# Esquematico.net
KiCad netlist of a schematic drawn in Altium Designer
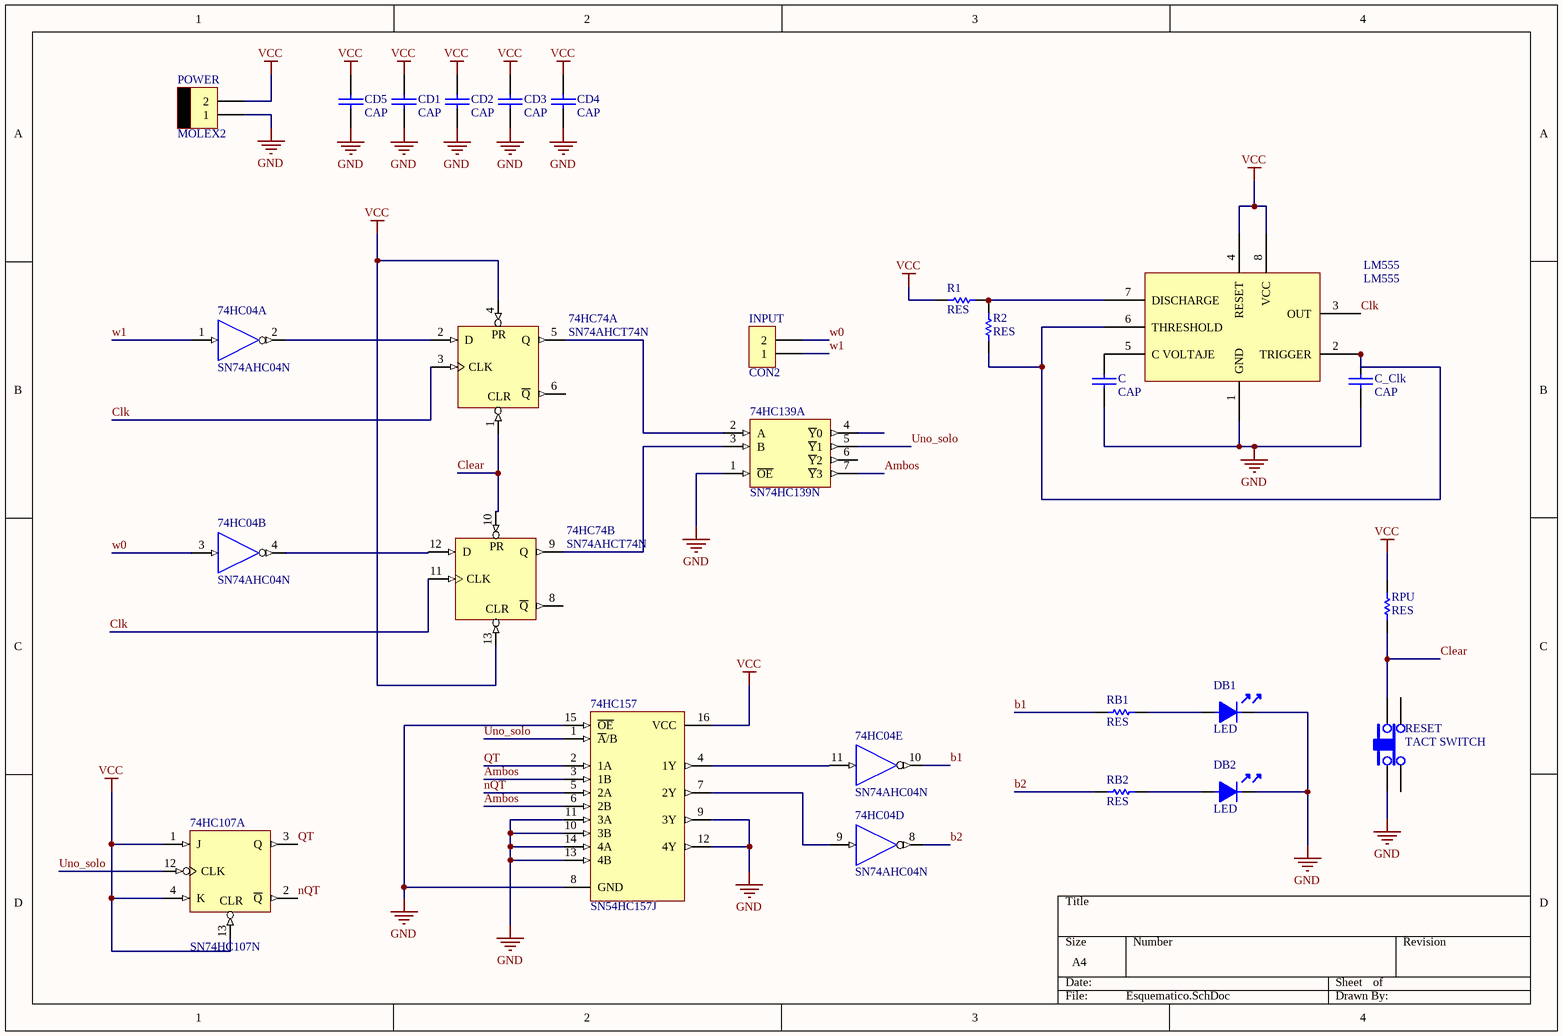
[diagram p0: Esquematico.SchDoc]

(export (version "E")
  (design (tool "Eeschema 10.0.6"))
  (components
    (comp (ref "74HC04")
      (value "SN74AHC04N")
      (footprint "N014")
      (description "Hex Inverter")
      (fields (field (name "PUBLISHER") "Altium Limited"))
      (libsource (lib "TI Logic Gate 1") (part "SN74AHC04N"))
    )
    (comp (ref "74HC74")
      (value "SN74AHCT74N")
      (footprint "N014")
      (description "Dual Positive-Edge-Triggered D-Type Flip-Flop with Clear and Preset")
      (fields (field (name "PUBLISHER") "Altium Limited"))
      (libsource (lib "TI Logic Flip-Flop") (part "SN74AHCT74N"))
    )
    (comp (ref "74HC107")
      (value "SN74HC107N")
      (footprint "N014D")
      (description "Dual J-K Negative-Edge-Triggered Flip-Flop with Clear")
      (fields (field (name "PUBLISHER") "Altium Limited"))
      (libsource (lib "TI Logic Flip-Flop") (part "SN74HC107N"))
    )
    (comp (ref "74HC139")
      (value "SN74HC139N")
      (footprint "N016")
      (description "Dual 2-Line to 4-Line Decoder / Demultiplexer")
      (fields (field (name "PUBLISHER") "Altium Limited"))
      (libsource (lib "TI Logic Decoder Demux") (part "SN74HC139N"))
    )
    (comp (ref "74HC157")
      (value "SN54HC157J")
      (footprint "J016")
      (description "Quadraple 2-Line to 1-Line Data Selector/Multiplexer")
      (fields (field (name "PUBLISHER") "Altium Limited"))
      (libsource (lib "TI Logic Multiplexer") (part "SN54HC157J"))
    )
    (comp (ref "C") (value "CAP") (footprint "CAP200") (libsource (lib "LIBEBAL") (part "CAP")))
    (comp (ref "CD1") (value "CAP") (footprint "CAP200") (libsource (lib "LIBEBAL") (part "CAP")))
    (comp (ref "CD2") (value "CAP") (footprint "CAP200") (libsource (lib "LIBEBAL") (part "CAP")))
    (comp (ref "CD3") (value "CAP") (footprint "CAP200") (libsource (lib "LIBEBAL") (part "CAP")))
    (comp (ref "CD4") (value "CAP") (footprint "CAP200") (libsource (lib "LIBEBAL") (part "CAP")))
    (comp (ref "CD5") (value "CAP") (footprint "CAP200") (libsource (lib "LIBEBAL") (part "CAP")))
    (comp (ref "C_Clk") (value "CAP") (footprint "CAP200") (libsource (lib "LIBEBAL") (part "CAP")))
    (comp (ref "DB1") (value "LED") (footprint "LED3") (libsource (lib "LIBEBAL") (part "LED")))
    (comp (ref "DB2") (value "LED") (footprint "LED3") (libsource (lib "LIBEBAL") (part "LED")))
    (comp (ref "INPUT") (value "CON2") (footprint "SIP2") (libsource (lib "LIBEBAL") (part "CON2")))
    (comp (ref "LM555")
      (value "LM555")
      (footprint "DIP8")
      (description "Timer")
      (libsource (lib "LIBEBAL") (part "LM555"))
    )
    (comp (ref "POWER") (value "MOLEX2") (footprint "MOLEX2") (libsource (lib "LIBEBAL") (part "MOLEX2")))
    (comp (ref "R1") (value "RES") (footprint "RES400") (libsource (lib "LIBEBAL") (part "RES")))
    (comp (ref "R2") (value "RES") (footprint "RES400") (libsource (lib "LIBEBAL") (part "RES")))
    (comp (ref "RB1") (value "RES") (footprint "RES400") (libsource (lib "LIBEBAL") (part "RES")))
    (comp (ref "RB2") (value "RES") (footprint "RES400") (libsource (lib "LIBEBAL") (part "RES")))
    (comp (ref "RESET")
      (value "TACT SWITCH")
      (footprint "TACTSWITCH")
      (libsource (lib "LIBEBAL") (part "TACT SWITCH"))
    )
    (comp (ref "RPU") (value "RES") (footprint "RES400") (libsource (lib "LIBEBAL") (part "RES")))
  )
  (nets
    (net (code "1") (name "/Ambos") (class "Default")
      (node (ref "74HC139") (pin "7") (pinfunction "~{Y}3_7") (pintype "output"))
      (node (ref "74HC157") (pin "3") (pinfunction "1B_3") (pintype "input"))
      (node (ref "74HC157") (pin "6") (pinfunction "2B_6") (pintype "input"))
    )
    (net (code "2") (name "/Clear") (class "Default")
      (node (ref "74HC74") (pin "1") (pinfunction "CLR_1") (pintype "input"))
      (node (ref "74HC74") (pin "10") (pinfunction "PR_10") (pintype "input"))
      (node (ref "RESET") (pin "3") (pinfunction "3_3") (pintype "passive"))
      (node (ref "RPU") (pin "1") (pinfunction "1_1") (pintype "passive"))
    )
    (net (code "3") (name "/Clk") (class "Default")
      (node (ref "74HC74") (pin "11") (pinfunction "CLK_11") (pintype "input"))
      (node (ref "74HC74") (pin "3") (pinfunction "CLK_3") (pintype "input"))
      (node (ref "LM555") (pin "3") (pinfunction "OUT_3") (pintype "passive"))
    )
    (net (code "4") (name "/QT") (class "Default")
      (node (ref "74HC107") (pin "3") (pinfunction "Q_3") (pintype "output"))
      (node (ref "74HC157") (pin "2") (pinfunction "1A_2") (pintype "input"))
    )
    (net (code "5") (name "/Uno_solo") (class "Default")
      (node (ref "74HC107") (pin "12") (pinfunction "CLK_12") (pintype "input"))
      (node (ref "74HC139") (pin "5") (pinfunction "~{Y}1_5") (pintype "output"))
      (node (ref "74HC157") (pin "1") (pinfunction "~{A}/B_1") (pintype "input"))
    )
    (net (code "6") (name "/b1") (class "Default")
      (node (ref "74HC04") (pin "10") (pinfunction "Y_10") (pintype "output"))
      (node (ref "RB1") (pin "1") (pinfunction "1_1") (pintype "passive"))
    )
    (net (code "7") (name "/b2") (class "Default")
      (node (ref "74HC04") (pin "8") (pinfunction "Y_8") (pintype "output"))
      (node (ref "RB2") (pin "1") (pinfunction "1_1") (pintype "passive"))
    )
    (net (code "8") (name "/nQT") (class "Default")
      (node (ref "74HC107") (pin "2") (pinfunction "~{Q}_2") (pintype "output"))
      (node (ref "74HC157") (pin "5") (pinfunction "2A_5") (pintype "input"))
    )
    (net (code "9") (name "/w0") (class "Default")
      (node (ref "74HC04") (pin "3") (pinfunction "A_3") (pintype "input"))
      (node (ref "INPUT") (pin "2") (pinfunction "2_2") (pintype "passive"))
    )
    (net (code "10") (name "/w1") (class "Default")
      (node (ref "74HC04") (pin "1") (pinfunction "A_1") (pintype "input"))
      (node (ref "INPUT") (pin "1") (pinfunction "1_1") (pintype "passive"))
    )
    (net (code "11") (name "GND") (class "Default")
      (node (ref "74HC04") (pin "7") (pinfunction "GND_7") (pintype "power_in"))
      (node (ref "74HC107") (pin "7") (pinfunction "GND_7") (pintype "power_in"))
      (node (ref "74HC139") (pin "1") (pinfunction "~{OE}_1") (pintype "input"))
      (node (ref "74HC139") (pin "8") (pinfunction "GND_8") (pintype "power_in"))
      (node (ref "74HC157") (pin "10") (pinfunction "3B_10") (pintype "input"))
      (node (ref "74HC157") (pin "11") (pinfunction "3A_11") (pintype "input"))
      (node (ref "74HC157") (pin "12") (pinfunction "4Y_12") (pintype "output"))
      (node (ref "74HC157") (pin "13") (pinfunction "4B_13") (pintype "input"))
      (node (ref "74HC157") (pin "14") (pinfunction "4A_14") (pintype "input"))
      (node (ref "74HC157") (pin "15") (pinfunction "~{OE}_15") (pintype "input"))
      (node (ref "74HC157") (pin "8") (pinfunction "GND_8") (pintype "power_in"))
      (node (ref "74HC157") (pin "9") (pinfunction "3Y_9") (pintype "output"))
      (node (ref "74HC74") (pin "7") (pinfunction "GND_7") (pintype "power_in"))
      (node (ref "C") (pin "2") (pinfunction "2_2") (pintype "passive"))
      (node (ref "CD1") (pin "2") (pinfunction "2_2") (pintype "passive"))
      (node (ref "CD2") (pin "2") (pinfunction "2_2") (pintype "passive"))
      (node (ref "CD3") (pin "2") (pinfunction "2_2") (pintype "passive"))
      (node (ref "CD4") (pin "2") (pinfunction "2_2") (pintype "passive"))
      (node (ref "CD5") (pin "2") (pinfunction "2_2") (pintype "passive"))
      (node (ref "C_Clk") (pin "2") (pinfunction "2_2") (pintype "passive"))
      (node (ref "DB1") (pin "2") (pinfunction "2_2") (pintype "passive"))
      (node (ref "DB2") (pin "2") (pinfunction "2_2") (pintype "passive"))
      (node (ref "LM555") (pin "1") (pinfunction "GND_1") (pintype "passive"))
      (node (ref "POWER") (pin "1") (pinfunction "1_1") (pintype "passive"))
      (node (ref "RESET") (pin "1") (pinfunction "1_1") (pintype "passive"))
    )
    (net (code "12") (name "Net-(74HC04A-Y)") (class "Default")
      (node (ref "74HC04") (pin "2") (pinfunction "Y_2") (pintype "output"))
      (node (ref "74HC74") (pin "2") (pinfunction "D_2") (pintype "input"))
    )
    (net (code "13") (name "Net-(74HC04B-Y)") (class "Default")
      (node (ref "74HC04") (pin "4") (pinfunction "Y_4") (pintype "output"))
      (node (ref "74HC74") (pin "12") (pinfunction "D_12") (pintype "input"))
    )
    (net (code "14") (name "Net-(74HC04D-A)") (class "Default")
      (node (ref "74HC04") (pin "9") (pinfunction "A_9") (pintype "input"))
      (node (ref "74HC157") (pin "7") (pinfunction "2Y_7") (pintype "output"))
    )
    (net (code "15") (name "Net-(74HC04E-A)") (class "Default")
      (node (ref "74HC04") (pin "11") (pinfunction "A_11") (pintype "input"))
      (node (ref "74HC157") (pin "4") (pinfunction "1Y_4") (pintype "output"))
    )
    (net (code "16") (name "Net-(74HC139A-A)") (class "Default")
      (node (ref "74HC139") (pin "2") (pinfunction "A_2") (pintype "input"))
      (node (ref "74HC74") (pin "5") (pinfunction "Q_5") (pintype "output"))
    )
    (net (code "17") (name "Net-(74HC139A-B)") (class "Default")
      (node (ref "74HC139") (pin "3") (pinfunction "B_3") (pintype "input"))
      (node (ref "74HC74") (pin "9") (pinfunction "Q_9") (pintype "output"))
    )
    (net (code "18") (name "Net-(DB1-Pad1)") (class "Default")
      (node (ref "DB1") (pin "1") (pinfunction "1_1") (pintype "passive"))
      (node (ref "RB1") (pin "2") (pinfunction "2_2") (pintype "passive"))
    )
    (net (code "19") (name "Net-(DB2-Pad1)") (class "Default")
      (node (ref "DB2") (pin "1") (pinfunction "1_1") (pintype "passive"))
      (node (ref "RB2") (pin "2") (pinfunction "2_2") (pintype "passive"))
    )
    (net (code "20") (name "Net-(LM555-C_VOLTAJE)") (class "Default")
      (node (ref "C") (pin "1") (pinfunction "1_1") (pintype "passive"))
      (node (ref "LM555") (pin "5") (pinfunction "C_VOLTAJE_5") (pintype "passive"))
    )
    (net (code "21") (name "Net-(LM555-DISCHARGE)") (class "Default")
      (node (ref "LM555") (pin "7") (pinfunction "DISCHARGE_7") (pintype "passive"))
      (node (ref "R1") (pin "2") (pinfunction "2_2") (pintype "passive"))
      (node (ref "R2") (pin "2") (pinfunction "2_2") (pintype "passive"))
    )
    (net (code "22") (name "Net-(LM555-THRESHOLD)") (class "Default")
      (node (ref "C_Clk") (pin "1") (pinfunction "1_1") (pintype "passive"))
      (node (ref "LM555") (pin "2") (pinfunction "TRIGGER_2") (pintype "passive"))
      (node (ref "LM555") (pin "6") (pinfunction "THRESHOLD_6") (pintype "passive"))
      (node (ref "R2") (pin "1") (pinfunction "1_1") (pintype "passive"))
    )
    (net (code "23") (name "VCC") (class "Default")
      (node (ref "74HC04") (pin "14") (pinfunction "VCC_14") (pintype "power_in"))
      (node (ref "74HC107") (pin "1") (pinfunction "J_1") (pintype "input"))
      (node (ref "74HC107") (pin "13") (pinfunction "CLR_13") (pintype "input"))
      (node (ref "74HC107") (pin "14") (pinfunction "VCC_14") (pintype "power_in"))
      (node (ref "74HC107") (pin "4") (pinfunction "K_4") (pintype "input"))
      (node (ref "74HC139") (pin "16") (pinfunction "VCC_16") (pintype "power_in"))
      (node (ref "74HC157") (pin "16") (pinfunction "VCC_16") (pintype "power_in"))
      (node (ref "74HC74") (pin "13") (pinfunction "CLR_13") (pintype "input"))
      (node (ref "74HC74") (pin "14") (pinfunction "VCC_14") (pintype "power_in"))
      (node (ref "74HC74") (pin "4") (pinfunction "PR_4") (pintype "input"))
      (node (ref "CD1") (pin "1") (pinfunction "1_1") (pintype "passive"))
      (node (ref "CD2") (pin "1") (pinfunction "1_1") (pintype "passive"))
      (node (ref "CD3") (pin "1") (pinfunction "1_1") (pintype "passive"))
      (node (ref "CD4") (pin "1") (pinfunction "1_1") (pintype "passive"))
      (node (ref "CD5") (pin "1") (pinfunction "1_1") (pintype "passive"))
      (node (ref "LM555") (pin "4") (pinfunction "RESET_4") (pintype "passive"))
      (node (ref "LM555") (pin "8") (pinfunction "VCC_8") (pintype "passive"))
      (node (ref "POWER") (pin "2") (pinfunction "2_2") (pintype "passive"))
      (node (ref "R1") (pin "1") (pinfunction "1_1") (pintype "passive"))
      (node (ref "RPU") (pin "2") (pinfunction "2_2") (pintype "passive"))
    )
    (net (code "24") (name "unconnected-(74HC74A-~{Q}-Pad6)") (class "Default")
      (node (ref "74HC74") (pin "6") (pinfunction "~{Q}_6") (pintype "output"))
    )
    (net (code "25") (name "unconnected-(74HC74B-~{Q}-Pad8)") (class "Default")
      (node (ref "74HC74") (pin "8") (pinfunction "~{Q}_8") (pintype "output"))
    )
    (net (code "26") (name "unconnected-(74HC139A-~{Y}0-Pad4)") (class "Default")
      (node (ref "74HC139") (pin "4") (pinfunction "~{Y}0_4") (pintype "output"))
    )
    (net (code "27") (name "unconnected-(74HC139A-~{Y}2-Pad6)") (class "Default")
      (node (ref "74HC139") (pin "6") (pinfunction "~{Y}2_6") (pintype "output"))
    )
    (net (code "28") (name "unconnected-(RESET-Pad2)") (class "Default")
      (node (ref "RESET") (pin "2") (pinfunction "2_2") (pintype "passive"))
    )
    (net (code "29") (name "unconnected-(RESET-Pad4)") (class "Default")
      (node (ref "RESET") (pin "4") (pinfunction "4_4") (pintype "passive"))
    )
  )
)
